# pov.net
KiCad netlist of a schematic drawn in EAGLE
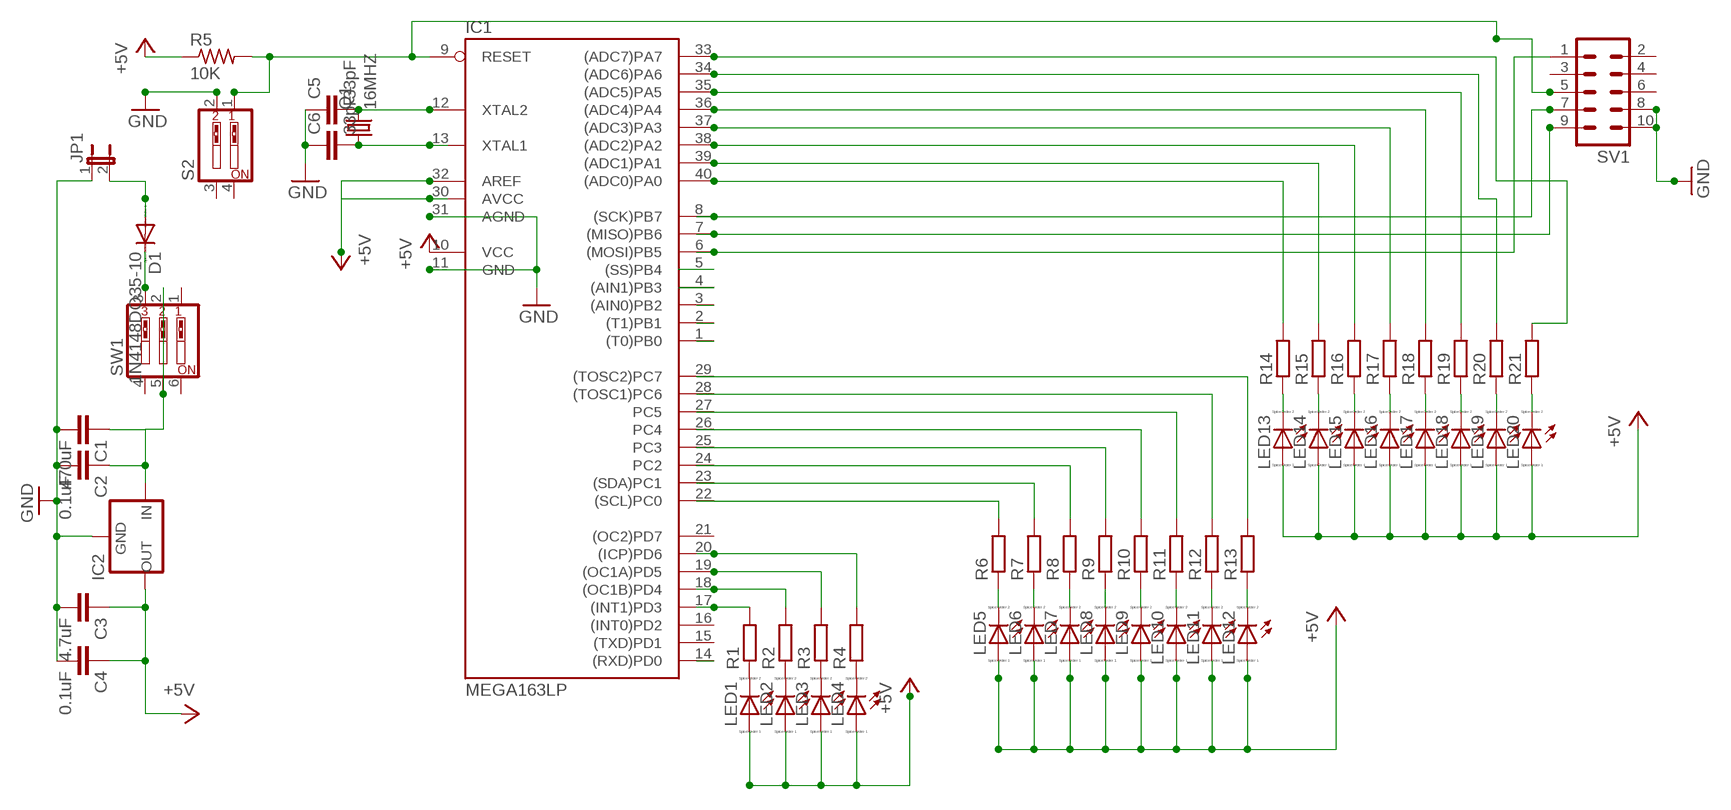
[diagram p0: schematic, sheet 1]

(export (version "E")
  (design (tool "Eeschema 10.0.6"))
  (components
    (comp (ref "C1")
      (value "470uF")
      (footprint "eagle-import:C2.5-4")
      (libsource (lib "eagle-import") (part "C2.5/4"))
    )
    (comp (ref "C2")
      (value "0.1uF")
      (footprint "eagle-import:C2.5-4")
      (libsource (lib "eagle-import") (part "C2.5/4"))
    )
    (comp (ref "C3")
      (value "4.7uF")
      (footprint "eagle-import:C2.5-4")
      (libsource (lib "eagle-import") (part "C2.5/4"))
    )
    (comp (ref "C4")
      (value "0.1uF")
      (footprint "eagle-import:C2.5-4")
      (libsource (lib "eagle-import") (part "C2.5/4"))
    )
    (comp (ref "C5")
      (value "33pF")
      (footprint "eagle-import:C2.5-4")
      (libsource (lib "eagle-import") (part "C2.5/4"))
    )
    (comp (ref "C6")
      (value "33pF")
      (footprint "eagle-import:C2.5-4")
      (libsource (lib "eagle-import") (part "C2.5/4"))
    )
    (comp (ref "D1")
      (value "1N4148DO35-10")
      (footprint "eagle-import:DO35-10")
      (libsource (lib "eagle-import") (part "1N4148DO35-10"))
    )
    (comp (ref "IC1")
      (value "MEGA163LP")
      (footprint "eagle-import:DIL40")
      (libsource (lib "eagle-import") (part "MEGA163PL"))
    )
    (comp (ref "IC2")
      (value "78XXS")
      (footprint "eagle-import:78XXS")
      (libsource (lib "eagle-import") (part "78XXS"))
    )
    (comp (ref "JP1")
      (value "JP1E")
      (footprint "eagle-import:JP1")
      (libsource (lib "eagle-import") (part "JP1E"))
    )
    (comp (ref "LED1")
      (value "LED_ELD260")
      (footprint "eagle-import:LED_LD260")
      (libsource (lib "eagle-import") (part "LED_ELD260"))
    )
    (comp (ref "LED2")
      (value "LED_ELD260")
      (footprint "eagle-import:LED_LD260")
      (libsource (lib "eagle-import") (part "LED_ELD260"))
    )
    (comp (ref "LED3")
      (value "LED_ELD260")
      (footprint "eagle-import:LED_LD260")
      (libsource (lib "eagle-import") (part "LED_ELD260"))
    )
    (comp (ref "LED4")
      (value "LED_ELD260")
      (footprint "eagle-import:LED_LD260")
      (libsource (lib "eagle-import") (part "LED_ELD260"))
    )
    (comp (ref "LED5")
      (value "LED_ELD260")
      (footprint "eagle-import:LED_LD260")
      (libsource (lib "eagle-import") (part "LED_ELD260"))
    )
    (comp (ref "LED6")
      (value "LED_ELD260")
      (footprint "eagle-import:LED_LD260")
      (libsource (lib "eagle-import") (part "LED_ELD260"))
    )
    (comp (ref "LED7")
      (value "LED_ELD260")
      (footprint "eagle-import:LED_LD260")
      (libsource (lib "eagle-import") (part "LED_ELD260"))
    )
    (comp (ref "LED8")
      (value "LED_ELD260")
      (footprint "eagle-import:LED_LD260")
      (libsource (lib "eagle-import") (part "LED_ELD260"))
    )
    (comp (ref "LED9")
      (value "LED_ELD260")
      (footprint "eagle-import:LED_LD260")
      (libsource (lib "eagle-import") (part "LED_ELD260"))
    )
    (comp (ref "LED10")
      (value "LED_ELD260")
      (footprint "eagle-import:LED_LD260")
      (libsource (lib "eagle-import") (part "LED_ELD260"))
    )
    (comp (ref "LED11")
      (value "LED_ELD260")
      (footprint "eagle-import:LED_LD260")
      (libsource (lib "eagle-import") (part "LED_ELD260"))
    )
    (comp (ref "LED12")
      (value "LED_ELD260")
      (footprint "eagle-import:LED_LD260")
      (libsource (lib "eagle-import") (part "LED_ELD260"))
    )
    (comp (ref "LED13")
      (value "LED_ELD260")
      (footprint "eagle-import:LED_LD260")
      (libsource (lib "eagle-import") (part "LED_ELD260"))
    )
    (comp (ref "LED14")
      (value "LED_ELD260")
      (footprint "eagle-import:LED_LD260")
      (libsource (lib "eagle-import") (part "LED_ELD260"))
    )
    (comp (ref "LED15")
      (value "LED_ELD260")
      (footprint "eagle-import:LED_LD260")
      (libsource (lib "eagle-import") (part "LED_ELD260"))
    )
    (comp (ref "LED16")
      (value "LED_ELD260")
      (footprint "eagle-import:LED_LD260")
      (libsource (lib "eagle-import") (part "LED_ELD260"))
    )
    (comp (ref "LED17")
      (value "LED_ELD260")
      (footprint "eagle-import:LED_LD260")
      (libsource (lib "eagle-import") (part "LED_ELD260"))
    )
    (comp (ref "LED18")
      (value "LED_ELD260")
      (footprint "eagle-import:LED_LD260")
      (libsource (lib "eagle-import") (part "LED_ELD260"))
    )
    (comp (ref "LED19")
      (value "LED_ELD260")
      (footprint "eagle-import:LED_LD260")
      (libsource (lib "eagle-import") (part "LED_ELD260"))
    )
    (comp (ref "LED20")
      (value "LED_ELD260")
      (footprint "eagle-import:LED_LD260")
      (libsource (lib "eagle-import") (part "LED_ELD260"))
    )
    (comp (ref "Q1")
      (value "16MHZ")
      (footprint "eagle-import:HC49U-V")
      (libsource (lib "eagle-import") (part "CRYSTALHC49U-V"))
    )
    (comp (ref "R1")
      (value "R-EU_0207/7")
      (footprint "eagle-import:0207_7")
      (libsource (lib "eagle-import") (part "R-EU_0207/7"))
    )
    (comp (ref "R2")
      (value "R-EU_0207/7")
      (footprint "eagle-import:0207_7")
      (libsource (lib "eagle-import") (part "R-EU_0207/7"))
    )
    (comp (ref "R3")
      (value "R-EU_0207/7")
      (footprint "eagle-import:0207_7")
      (libsource (lib "eagle-import") (part "R-EU_0207/7"))
    )
    (comp (ref "R4")
      (value "R-EU_0207/7")
      (footprint "eagle-import:0207_7")
      (libsource (lib "eagle-import") (part "R-EU_0207/7"))
    )
    (comp (ref "R5")
      (value "10K")
      (footprint "eagle-import:0204_7")
      (libsource (lib "eagle-import") (part "R-US_0204/7"))
    )
    (comp (ref "R6")
      (value "R-EU_0207/7")
      (footprint "eagle-import:0207_7")
      (libsource (lib "eagle-import") (part "R-EU_0207/7"))
    )
    (comp (ref "R7")
      (value "R-EU_0207/7")
      (footprint "eagle-import:0207_7")
      (libsource (lib "eagle-import") (part "R-EU_0207/7"))
    )
    (comp (ref "R8")
      (value "R-EU_0207/7")
      (footprint "eagle-import:0207_7")
      (libsource (lib "eagle-import") (part "R-EU_0207/7"))
    )
    (comp (ref "R9")
      (value "R-EU_0207/7")
      (footprint "eagle-import:0207_7")
      (libsource (lib "eagle-import") (part "R-EU_0207/7"))
    )
    (comp (ref "R10")
      (value "R-EU_0207/7")
      (footprint "eagle-import:0207_7")
      (libsource (lib "eagle-import") (part "R-EU_0207/7"))
    )
    (comp (ref "R11")
      (value "R-EU_0207/7")
      (footprint "eagle-import:0207_7")
      (libsource (lib "eagle-import") (part "R-EU_0207/7"))
    )
    (comp (ref "R12")
      (value "R-EU_0207/7")
      (footprint "eagle-import:0207_7")
      (libsource (lib "eagle-import") (part "R-EU_0207/7"))
    )
    (comp (ref "R13")
      (value "R-EU_0207/7")
      (footprint "eagle-import:0207_7")
      (libsource (lib "eagle-import") (part "R-EU_0207/7"))
    )
    (comp (ref "R14")
      (value "R-EU_0207/7")
      (footprint "eagle-import:0207_7")
      (libsource (lib "eagle-import") (part "R-EU_0207/7"))
    )
    (comp (ref "R15")
      (value "R-EU_0207/7")
      (footprint "eagle-import:0207_7")
      (libsource (lib "eagle-import") (part "R-EU_0207/7"))
    )
    (comp (ref "R16")
      (value "R-EU_0207/7")
      (footprint "eagle-import:0207_7")
      (libsource (lib "eagle-import") (part "R-EU_0207/7"))
    )
    (comp (ref "R17")
      (value "R-EU_0207/7")
      (footprint "eagle-import:0207_7")
      (libsource (lib "eagle-import") (part "R-EU_0207/7"))
    )
    (comp (ref "R18")
      (value "R-EU_0207/7")
      (footprint "eagle-import:0207_7")
      (libsource (lib "eagle-import") (part "R-EU_0207/7"))
    )
    (comp (ref "R19")
      (value "R-EU_0207/7")
      (footprint "eagle-import:0207_7")
      (libsource (lib "eagle-import") (part "R-EU_0207/7"))
    )
    (comp (ref "R20")
      (value "R-EU_0207/7")
      (footprint "eagle-import:0207_7")
      (libsource (lib "eagle-import") (part "R-EU_0207/7"))
    )
    (comp (ref "R21")
      (value "R-EU_0207/7")
      (footprint "eagle-import:0207_7")
      (libsource (lib "eagle-import") (part "R-EU_0207/7"))
    )
    (comp (ref "S2")
      (value "SW_DIP-2")
      (footprint "eagle-import:EDG-02")
      (libsource (lib "eagle-import") (part "SW_DIP-2"))
    )
    (comp (ref "SV1")
      (value "MA05-2")
      (footprint "eagle-import:MA05-2")
      (libsource (lib "eagle-import") (part "MA05-2"))
    )
    (comp (ref "SW1")
      (value "SW_DIP-3")
      (footprint "eagle-import:EDG-03")
      (libsource (lib "eagle-import") (part "SW_DIP-3"))
    )
  )
  (nets
    (net (code "1") (name "+5V") (class "Default")
      (node (ref "C3") (pin "1") (pinfunction "1_1") (pintype "passive"))
      (node (ref "C4") (pin "1") (pinfunction "1_1") (pintype "passive"))
      (node (ref "IC1") (pin "10") (pinfunction "VCC_10") (pintype "power_in"))
      (node (ref "IC1") (pin "30") (pinfunction "AVCC_30") (pintype "power_in"))
      (node (ref "IC1") (pin "32") (pinfunction "AREF_32") (pintype "passive"))
      (node (ref "IC2") (pin "OUT") (pinfunction "OUT_OUT") (pintype "passive"))
      (node (ref "LED1") (pin "A") (pinfunction "A_A") (pintype "passive"))
      (node (ref "LED10") (pin "A") (pinfunction "A_A") (pintype "passive"))
      (node (ref "LED11") (pin "A") (pinfunction "A_A") (pintype "passive"))
      (node (ref "LED12") (pin "A") (pinfunction "A_A") (pintype "passive"))
      (node (ref "LED13") (pin "A") (pinfunction "A_A") (pintype "passive"))
      (node (ref "LED14") (pin "A") (pinfunction "A_A") (pintype "passive"))
      (node (ref "LED15") (pin "A") (pinfunction "A_A") (pintype "passive"))
      (node (ref "LED16") (pin "A") (pinfunction "A_A") (pintype "passive"))
      (node (ref "LED17") (pin "A") (pinfunction "A_A") (pintype "passive"))
      (node (ref "LED18") (pin "A") (pinfunction "A_A") (pintype "passive"))
      (node (ref "LED19") (pin "A") (pinfunction "A_A") (pintype "passive"))
      (node (ref "LED2") (pin "A") (pinfunction "A_A") (pintype "passive"))
      (node (ref "LED20") (pin "A") (pinfunction "A_A") (pintype "passive"))
      (node (ref "LED3") (pin "A") (pinfunction "A_A") (pintype "passive"))
      (node (ref "LED4") (pin "A") (pinfunction "A_A") (pintype "passive"))
      (node (ref "LED5") (pin "A") (pinfunction "A_A") (pintype "passive"))
      (node (ref "LED6") (pin "A") (pinfunction "A_A") (pintype "passive"))
      (node (ref "LED7") (pin "A") (pinfunction "A_A") (pintype "passive"))
      (node (ref "LED8") (pin "A") (pinfunction "A_A") (pintype "passive"))
      (node (ref "LED9") (pin "A") (pinfunction "A_A") (pintype "passive"))
      (node (ref "R5") (pin "1") (pinfunction "1_1") (pintype "passive"))
    )
    (net (code "2") (name "GND") (class "Default")
      (node (ref "C1") (pin "2") (pinfunction "2_2") (pintype "passive"))
      (node (ref "C2") (pin "2") (pinfunction "2_2") (pintype "passive"))
      (node (ref "C3") (pin "2") (pinfunction "2_2") (pintype "passive"))
      (node (ref "C4") (pin "2") (pinfunction "2_2") (pintype "passive"))
      (node (ref "C5") (pin "1") (pinfunction "1_1") (pintype "passive"))
      (node (ref "C6") (pin "1") (pinfunction "1_1") (pintype "passive"))
      (node (ref "IC1") (pin "11") (pinfunction "GND_11") (pintype "power_in"))
      (node (ref "IC1") (pin "31") (pinfunction "AGND_31") (pintype "power_in"))
      (node (ref "IC2") (pin "GND") (pinfunction "GND_GND") (pintype "input"))
      (node (ref "JP1") (pin "1") (pinfunction "1_1") (pintype "passive"))
      (node (ref "S2") (pin "2") (pinfunction "2_2") (pintype "passive"))
      (node (ref "SV1") (pin "10") (pinfunction "10_10") (pintype "passive"))
      (node (ref "SV1") (pin "8") (pinfunction "8_8") (pintype "passive"))
    )
    (net (code "3") (name "Net-(C1-Pad1)") (class "Default")
      (node (ref "C1") (pin "1") (pinfunction "1_1") (pintype "passive"))
      (node (ref "C2") (pin "1") (pinfunction "1_1") (pintype "passive"))
      (node (ref "IC2") (pin "IN") (pinfunction "IN_IN") (pintype "input"))
      (node (ref "SW1") (pin "2") (pinfunction "2_2") (pintype "passive"))
      (node (ref "SW1") (pin "5") (pinfunction "5_5") (pintype "passive"))
    )
    (net (code "4") (name "Net-(D1-PadA)") (class "Default")
      (node (ref "D1") (pin "A") (pinfunction "A_A") (pintype "passive"))
      (node (ref "JP1") (pin "2") (pinfunction "2_2") (pintype "passive"))
    )
    (net (code "5") (name "Net-(D1-PadC)") (class "Default")
      (node (ref "D1") (pin "C") (pinfunction "C_C") (pintype "passive"))
      (node (ref "SW1") (pin "3") (pinfunction "3_3") (pintype "passive"))
    )
    (net (code "6") (name "Net-(IC1-(ADC0)PA0)") (class "Default")
      (node (ref "IC1") (pin "40") (pinfunction "(ADC0)PA0_40") (pintype "bidirectional"))
      (node (ref "R14") (pin "2") (pinfunction "2_2") (pintype "passive"))
    )
    (net (code "7") (name "Net-(IC1-(ADC1)PA1)") (class "Default")
      (node (ref "IC1") (pin "39") (pinfunction "(ADC1)PA1_39") (pintype "bidirectional"))
      (node (ref "R15") (pin "2") (pinfunction "2_2") (pintype "passive"))
    )
    (net (code "8") (name "Net-(IC1-(ADC2)PA2)") (class "Default")
      (node (ref "IC1") (pin "38") (pinfunction "(ADC2)PA2_38") (pintype "bidirectional"))
      (node (ref "R16") (pin "2") (pinfunction "2_2") (pintype "passive"))
    )
    (net (code "9") (name "Net-(IC1-(ADC3)PA3)") (class "Default")
      (node (ref "IC1") (pin "37") (pinfunction "(ADC3)PA3_37") (pintype "bidirectional"))
      (node (ref "R17") (pin "2") (pinfunction "2_2") (pintype "passive"))
    )
    (net (code "10") (name "Net-(IC1-(ADC4)PA4)") (class "Default")
      (node (ref "IC1") (pin "36") (pinfunction "(ADC4)PA4_36") (pintype "bidirectional"))
      (node (ref "R18") (pin "2") (pinfunction "2_2") (pintype "passive"))
    )
    (net (code "11") (name "Net-(IC1-(ADC5)PA5)") (class "Default")
      (node (ref "IC1") (pin "35") (pinfunction "(ADC5)PA5_35") (pintype "bidirectional"))
      (node (ref "R19") (pin "2") (pinfunction "2_2") (pintype "passive"))
    )
    (net (code "12") (name "Net-(IC1-(ADC6)PA6)") (class "Default")
      (node (ref "IC1") (pin "34") (pinfunction "(ADC6)PA6_34") (pintype "bidirectional"))
      (node (ref "R20") (pin "2") (pinfunction "2_2") (pintype "passive"))
    )
    (net (code "13") (name "Net-(IC1-(ADC7)PA7)") (class "Default")
      (node (ref "IC1") (pin "33") (pinfunction "(ADC7)PA7_33") (pintype "bidirectional"))
      (node (ref "R21") (pin "2") (pinfunction "2_2") (pintype "passive"))
    )
    (net (code "14") (name "Net-(IC1-(ICP)PD6)") (class "Default")
      (node (ref "IC1") (pin "20") (pinfunction "(ICP)PD6_20") (pintype "bidirectional"))
      (node (ref "R4") (pin "2") (pinfunction "2_2") (pintype "passive"))
    )
    (net (code "15") (name "Net-(IC1-(INT1)PD3)") (class "Default")
      (node (ref "IC1") (pin "17") (pinfunction "(INT1)PD3_17") (pintype "bidirectional"))
      (node (ref "R1") (pin "2") (pinfunction "2_2") (pintype "passive"))
    )
    (net (code "16") (name "Net-(IC1-(MISO)PB6)") (class "Default")
      (node (ref "IC1") (pin "7") (pinfunction "(MISO)PB6_7") (pintype "bidirectional"))
      (node (ref "SV1") (pin "9") (pinfunction "9_9") (pintype "passive"))
    )
    (net (code "17") (name "Net-(IC1-(MOSI)PB5)") (class "Default")
      (node (ref "IC1") (pin "6") (pinfunction "(MOSI)PB5_6") (pintype "bidirectional"))
      (node (ref "SV1") (pin "1") (pinfunction "1_1") (pintype "passive"))
    )
    (net (code "18") (name "Net-(IC1-(OC1A)PD5)") (class "Default")
      (node (ref "IC1") (pin "19") (pinfunction "(OC1A)PD5_19") (pintype "bidirectional"))
      (node (ref "R3") (pin "2") (pinfunction "2_2") (pintype "passive"))
    )
    (net (code "19") (name "Net-(IC1-(OC1B)PD4)") (class "Default")
      (node (ref "IC1") (pin "18") (pinfunction "(OC1B)PD4_18") (pintype "bidirectional"))
      (node (ref "R2") (pin "2") (pinfunction "2_2") (pintype "passive"))
    )
    (net (code "20") (name "Net-(IC1-(SCK)PB7)") (class "Default")
      (node (ref "IC1") (pin "8") (pinfunction "(SCK)PB7_8") (pintype "bidirectional"))
      (node (ref "SV1") (pin "7") (pinfunction "7_7") (pintype "passive"))
    )
    (net (code "21") (name "Net-(IC1-(SCL)PC0)") (class "Default")
      (node (ref "IC1") (pin "22") (pinfunction "(SCL)PC0_22") (pintype "bidirectional"))
      (node (ref "R6") (pin "2") (pinfunction "2_2") (pintype "passive"))
    )
    (net (code "22") (name "Net-(IC1-(SDA)PC1)") (class "Default")
      (node (ref "IC1") (pin "23") (pinfunction "(SDA)PC1_23") (pintype "bidirectional"))
      (node (ref "R7") (pin "2") (pinfunction "2_2") (pintype "passive"))
    )
    (net (code "23") (name "Net-(IC1-(TOSC1)PC6)") (class "Default")
      (node (ref "IC1") (pin "28") (pinfunction "(TOSC1)PC6_28") (pintype "bidirectional"))
      (node (ref "R12") (pin "2") (pinfunction "2_2") (pintype "passive"))
    )
    (net (code "24") (name "Net-(IC1-(TOSC2)PC7)") (class "Default")
      (node (ref "IC1") (pin "29") (pinfunction "(TOSC2)PC7_29") (pintype "bidirectional"))
      (node (ref "R13") (pin "2") (pinfunction "2_2") (pintype "passive"))
    )
    (net (code "25") (name "Net-(IC1-PC2)") (class "Default")
      (node (ref "IC1") (pin "24") (pinfunction "PC2_24") (pintype "bidirectional"))
      (node (ref "R8") (pin "2") (pinfunction "2_2") (pintype "passive"))
    )
    (net (code "26") (name "Net-(IC1-PC3)") (class "Default")
      (node (ref "IC1") (pin "25") (pinfunction "PC3_25") (pintype "bidirectional"))
      (node (ref "R9") (pin "2") (pinfunction "2_2") (pintype "passive"))
    )
    (net (code "27") (name "Net-(IC1-PC4)") (class "Default")
      (node (ref "IC1") (pin "26") (pinfunction "PC4_26") (pintype "bidirectional"))
      (node (ref "R10") (pin "2") (pinfunction "2_2") (pintype "passive"))
    )
    (net (code "28") (name "Net-(IC1-PC5)") (class "Default")
      (node (ref "IC1") (pin "27") (pinfunction "PC5_27") (pintype "bidirectional"))
      (node (ref "R11") (pin "2") (pinfunction "2_2") (pintype "passive"))
    )
    (net (code "29") (name "Net-(IC1-RESET)") (class "Default")
      (node (ref "IC1") (pin "9") (pinfunction "RESET_9") (pintype "input"))
      (node (ref "R5") (pin "2") (pinfunction "2_2") (pintype "passive"))
      (node (ref "S2") (pin "1") (pinfunction "1_1") (pintype "passive"))
      (node (ref "SV1") (pin "5") (pinfunction "5_5") (pintype "passive"))
    )
    (net (code "30") (name "Net-(IC1-XTAL1)") (class "Default")
      (node (ref "C6") (pin "2") (pinfunction "2_2") (pintype "passive"))
      (node (ref "IC1") (pin "13") (pinfunction "XTAL1_13") (pintype "bidirectional"))
      (node (ref "Q1") (pin "1") (pinfunction "1_1") (pintype "passive"))
    )
    (net (code "31") (name "Net-(IC1-XTAL2)") (class "Default")
      (node (ref "C5") (pin "2") (pinfunction "2_2") (pintype "passive"))
      (node (ref "IC1") (pin "12") (pinfunction "XTAL2_12") (pintype "bidirectional"))
      (node (ref "Q1") (pin "2") (pinfunction "2_2") (pintype "passive"))
    )
    (net (code "32") (name "Net-(LED1-C)") (class "Default")
      (node (ref "LED1") (pin "K") (pinfunction "C_K") (pintype "passive"))
      (node (ref "R1") (pin "1") (pinfunction "1_1") (pintype "passive"))
    )
    (net (code "33") (name "Net-(LED2-C)") (class "Default")
      (node (ref "LED2") (pin "K") (pinfunction "C_K") (pintype "passive"))
      (node (ref "R2") (pin "1") (pinfunction "1_1") (pintype "passive"))
    )
    (net (code "34") (name "Net-(LED3-C)") (class "Default")
      (node (ref "LED3") (pin "K") (pinfunction "C_K") (pintype "passive"))
      (node (ref "R3") (pin "1") (pinfunction "1_1") (pintype "passive"))
    )
    (net (code "35") (name "Net-(LED4-C)") (class "Default")
      (node (ref "LED4") (pin "K") (pinfunction "C_K") (pintype "passive"))
      (node (ref "R4") (pin "1") (pinfunction "1_1") (pintype "passive"))
    )
    (net (code "36") (name "Net-(LED5-C)") (class "Default")
      (node (ref "LED5") (pin "K") (pinfunction "C_K") (pintype "passive"))
      (node (ref "R6") (pin "1") (pinfunction "1_1") (pintype "passive"))
    )
    (net (code "37") (name "Net-(LED6-C)") (class "Default")
      (node (ref "LED6") (pin "K") (pinfunction "C_K") (pintype "passive"))
      (node (ref "R7") (pin "1") (pinfunction "1_1") (pintype "passive"))
    )
    (net (code "38") (name "Net-(LED7-C)") (class "Default")
      (node (ref "LED7") (pin "K") (pinfunction "C_K") (pintype "passive"))
      (node (ref "R8") (pin "1") (pinfunction "1_1") (pintype "passive"))
    )
    (net (code "39") (name "Net-(LED8-C)") (class "Default")
      (node (ref "LED8") (pin "K") (pinfunction "C_K") (pintype "passive"))
      (node (ref "R9") (pin "1") (pinfunction "1_1") (pintype "passive"))
    )
    (net (code "40") (name "Net-(LED9-C)") (class "Default")
      (node (ref "LED9") (pin "K") (pinfunction "C_K") (pintype "passive"))
      (node (ref "R10") (pin "1") (pinfunction "1_1") (pintype "passive"))
    )
    (net (code "41") (name "Net-(LED10-C)") (class "Default")
      (node (ref "LED10") (pin "K") (pinfunction "C_K") (pintype "passive"))
      (node (ref "R11") (pin "1") (pinfunction "1_1") (pintype "passive"))
    )
    (net (code "42") (name "Net-(LED11-C)") (class "Default")
      (node (ref "LED11") (pin "K") (pinfunction "C_K") (pintype "passive"))
      (node (ref "R12") (pin "1") (pinfunction "1_1") (pintype "passive"))
    )
    (net (code "43") (name "Net-(LED12-C)") (class "Default")
      (node (ref "LED12") (pin "K") (pinfunction "C_K") (pintype "passive"))
      (node (ref "R13") (pin "1") (pinfunction "1_1") (pintype "passive"))
    )
    (net (code "44") (name "Net-(LED13-C)") (class "Default")
      (node (ref "LED13") (pin "K") (pinfunction "C_K") (pintype "passive"))
      (node (ref "R14") (pin "1") (pinfunction "1_1") (pintype "passive"))
    )
    (net (code "45") (name "Net-(LED14-C)") (class "Default")
      (node (ref "LED14") (pin "K") (pinfunction "C_K") (pintype "passive"))
      (node (ref "R15") (pin "1") (pinfunction "1_1") (pintype "passive"))
    )
    (net (code "46") (name "Net-(LED15-C)") (class "Default")
      (node (ref "LED15") (pin "K") (pinfunction "C_K") (pintype "passive"))
      (node (ref "R16") (pin "1") (pinfunction "1_1") (pintype "passive"))
    )
    (net (code "47") (name "Net-(LED16-C)") (class "Default")
      (node (ref "LED16") (pin "K") (pinfunction "C_K") (pintype "passive"))
      (node (ref "R17") (pin "1") (pinfunction "1_1") (pintype "passive"))
    )
    (net (code "48") (name "Net-(LED17-C)") (class "Default")
      (node (ref "LED17") (pin "K") (pinfunction "C_K") (pintype "passive"))
      (node (ref "R18") (pin "1") (pinfunction "1_1") (pintype "passive"))
    )
    (net (code "49") (name "Net-(LED18-C)") (class "Default")
      (node (ref "LED18") (pin "K") (pinfunction "C_K") (pintype "passive"))
      (node (ref "R19") (pin "1") (pinfunction "1_1") (pintype "passive"))
    )
    (net (code "50") (name "Net-(LED19-C)") (class "Default")
      (node (ref "LED19") (pin "K") (pinfunction "C_K") (pintype "passive"))
      (node (ref "R20") (pin "1") (pinfunction "1_1") (pintype "passive"))
    )
    (net (code "51") (name "Net-(LED20-C)") (class "Default")
      (node (ref "LED20") (pin "K") (pinfunction "C_K") (pintype "passive"))
      (node (ref "R21") (pin "1") (pinfunction "1_1") (pintype "passive"))
    )
    (net (code "52") (name "unconnected-(IC1-(AIN0)PB2-Pad3)") (class "Default")
      (node (ref "IC1") (pin "3") (pinfunction "(AIN0)PB2_3") (pintype "bidirectional"))
    )
    (net (code "53") (name "unconnected-(IC1-(AIN1)PB3-Pad4)") (class "Default")
      (node (ref "IC1") (pin "4") (pinfunction "(AIN1)PB3_4") (pintype "bidirectional"))
    )
    (net (code "54") (name "unconnected-(IC1-(INT0)PD2-Pad16)") (class "Default")
      (node (ref "IC1") (pin "16") (pinfunction "(INT0)PD2_16") (pintype "bidirectional"))
    )
    (net (code "55") (name "unconnected-(IC1-(OC2)PD7-Pad21)") (class "Default")
      (node (ref "IC1") (pin "21") (pinfunction "(OC2)PD7_21") (pintype "bidirectional"))
    )
    (net (code "56") (name "unconnected-(IC1-(RXD)PD0-Pad14)") (class "Default")
      (node (ref "IC1") (pin "14") (pinfunction "(RXD)PD0_14") (pintype "bidirectional"))
    )
    (net (code "57") (name "unconnected-(IC1-(SS)PB4-Pad5)") (class "Default")
      (node (ref "IC1") (pin "5") (pinfunction "(SS)PB4_5") (pintype "bidirectional"))
    )
    (net (code "58") (name "unconnected-(IC1-(T0)PB0-Pad1)") (class "Default")
      (node (ref "IC1") (pin "1") (pinfunction "(T0)PB0_1") (pintype "bidirectional"))
    )
    (net (code "59") (name "unconnected-(IC1-(T1)PB1-Pad2)") (class "Default")
      (node (ref "IC1") (pin "2") (pinfunction "(T1)PB1_2") (pintype "bidirectional"))
    )
    (net (code "60") (name "unconnected-(IC1-(TXD)PD1-Pad15)") (class "Default")
      (node (ref "IC1") (pin "15") (pinfunction "(TXD)PD1_15") (pintype "bidirectional"))
    )
    (net (code "61") (name "unconnected-(S2-Pad3)") (class "Default")
      (node (ref "S2") (pin "3") (pinfunction "3_3") (pintype "passive"))
    )
    (net (code "62") (name "unconnected-(S2-Pad4)") (class "Default")
      (node (ref "S2") (pin "4") (pinfunction "4_4") (pintype "passive"))
    )
    (net (code "63") (name "unconnected-(SV1-Pad2)") (class "Default")
      (node (ref "SV1") (pin "2") (pinfunction "2_2") (pintype "passive"))
    )
    (net (code "64") (name "unconnected-(SV1-Pad3)") (class "Default")
      (node (ref "SV1") (pin "3") (pinfunction "3_3") (pintype "passive"))
    )
    (net (code "65") (name "unconnected-(SV1-Pad4)") (class "Default")
      (node (ref "SV1") (pin "4") (pinfunction "4_4") (pintype "passive"))
    )
    (net (code "66") (name "unconnected-(SV1-Pad6)") (class "Default")
      (node (ref "SV1") (pin "6") (pinfunction "6_6") (pintype "passive"))
    )
    (net (code "67") (name "unconnected-(SW1-Pad1)") (class "Default")
      (node (ref "SW1") (pin "1") (pinfunction "1_1") (pintype "passive"))
    )
    (net (code "68") (name "unconnected-(SW1-Pad4)") (class "Default")
      (node (ref "SW1") (pin "4") (pinfunction "4_4") (pintype "passive"))
    )
    (net (code "69") (name "unconnected-(SW1-Pad6)") (class "Default")
      (node (ref "SW1") (pin "6") (pinfunction "6_6") (pintype "passive"))
    )
  )
)
